# Altium_fpga.net
KiCad netlist of a schematic drawn in Altium Designer
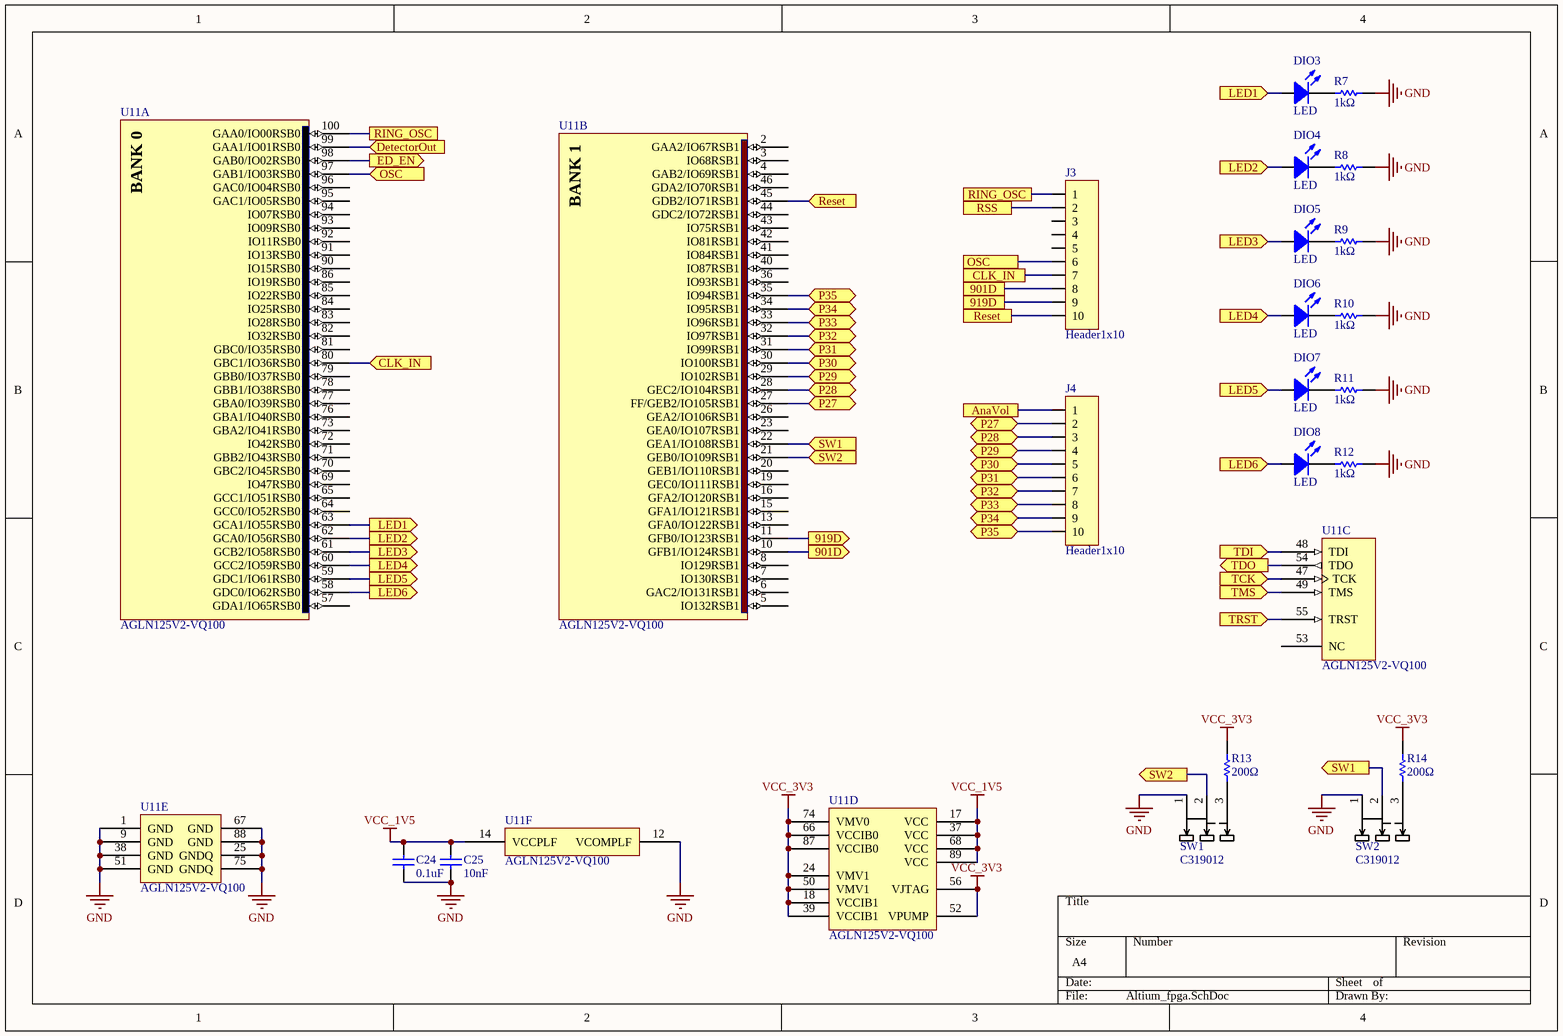
[diagram p0: Altium_fpga.SchDoc]

(export (version "E")
  (design (tool "Eeschema 10.0.6"))
  (components
    (comp (ref "C24") (value "0.1uF") (footprint "C0603") (libsource (lib "backscatter") (part "Cap")))
    (comp (ref "C25") (value "10nF") (footprint "C0603") (libsource (lib "backscatter") (part "Cap")))
    (comp (ref "DIO3") (value "LED") (footprint "LED0603") (libsource (lib "backscatter") (part "LED")))
    (comp (ref "DIO4") (value "LED") (footprint "LED0603") (libsource (lib "backscatter") (part "LED")))
    (comp (ref "DIO5") (value "LED") (footprint "LED0603") (libsource (lib "backscatter") (part "LED")))
    (comp (ref "DIO6") (value "LED") (footprint "LED0603") (libsource (lib "backscatter") (part "LED")))
    (comp (ref "DIO7") (value "LED") (footprint "LED0603") (libsource (lib "backscatter") (part "LED")))
    (comp (ref "DIO8") (value "LED") (footprint "LED0603") (libsource (lib "backscatter") (part "LED")))
    (comp (ref "J3")
      (value "Header1x10")
      (footprint "Header1x10")
      (libsource (lib "backscatter") (part "Header1x10"))
    )
    (comp (ref "J4")
      (value "Header1x10")
      (footprint "Header1x10")
      (libsource (lib "backscatter") (part "Header1x10"))
    )
    (comp (ref "R7") (value "1kΩ") (footprint "R0603") (libsource (lib "backscatter") (part "Res")))
    (comp (ref "R8") (value "1kΩ") (footprint "R0603") (libsource (lib "backscatter") (part "Res")))
    (comp (ref "R9") (value "1kΩ") (footprint "R0603") (libsource (lib "backscatter") (part "Res")))
    (comp (ref "R10") (value "1kΩ") (footprint "R0603") (libsource (lib "backscatter") (part "Res")))
    (comp (ref "R11") (value "1kΩ") (footprint "R0603") (libsource (lib "backscatter") (part "Res")))
    (comp (ref "R12") (value "1kΩ") (footprint "R0603") (libsource (lib "backscatter") (part "Res")))
    (comp (ref "R13") (value "200Ω") (footprint "R0603") (libsource (lib "backscatter") (part "Res")))
    (comp (ref "R14") (value "200Ω") (footprint "R0603") (libsource (lib "backscatter") (part "Res")))
    (comp (ref "SW1")
      (value "C319012")
      (footprint "C319012")
      (libsource (lib "backscatter") (part "C319012"))
    )
    (comp (ref "SW2")
      (value "C319012")
      (footprint "C319012")
      (libsource (lib "backscatter") (part "C319012"))
    )
    (comp (ref "U11")
      (value "AGLN125V2-VQ100")
      (footprint "VQ100_N")
      (libsource (lib "Actel IGLOO nano") (part "AGLN125V2-VQ100"))
    )
  )
  (nets
    (net (code "1") (name "/901D") (class "Default")
      (node (ref "J3") (pin "8") (pinfunction "8_8") (pintype "passive"))
      (node (ref "U11") (pin "10") (pinfunction "GFB1/IO124RSB1_10") (pintype "bidirectional"))
    )
    (net (code "2") (name "/919D") (class "Default")
      (node (ref "J3") (pin "9") (pinfunction "9_9") (pintype "passive"))
      (node (ref "U11") (pin "11") (pinfunction "GFB0/IO123RSB1_11") (pintype "bidirectional"))
    )
    (net (code "3") (name "/AnaVol") (class "Default")
      (node (ref "J4") (pin "1") (pinfunction "1_1") (pintype "passive"))
    )
    (net (code "4") (name "/CLK_IN") (class "Default")
      (node (ref "J3") (pin "7") (pinfunction "7_7") (pintype "passive"))
      (node (ref "U11") (pin "80") (pinfunction "GBC1/IO36RSB0_80") (pintype "bidirectional"))
    )
    (net (code "5") (name "/DetectorOut") (class "Default")
      (node (ref "U11") (pin "99") (pinfunction "GAA1/IO01RSB0_99") (pintype "bidirectional"))
    )
    (net (code "6") (name "/ED_EN") (class "Default")
      (node (ref "U11") (pin "98") (pinfunction "GAB0/IO02RSB0_98") (pintype "bidirectional"))
    )
    (net (code "7") (name "/LED1") (class "Default")
      (node (ref "DIO3") (pin "1") (pinfunction "*_1") (pintype "passive"))
      (node (ref "U11") (pin "63") (pinfunction "GCA1/IO55RSB0_63") (pintype "bidirectional"))
    )
    (net (code "8") (name "/LED2") (class "Default")
      (node (ref "DIO4") (pin "1") (pinfunction "*_1") (pintype "passive"))
      (node (ref "U11") (pin "62") (pinfunction "GCA0/IO56RSB0_62") (pintype "bidirectional"))
    )
    (net (code "9") (name "/LED3") (class "Default")
      (node (ref "DIO5") (pin "1") (pinfunction "*_1") (pintype "passive"))
      (node (ref "U11") (pin "61") (pinfunction "GCB2/IO58RSB0_61") (pintype "bidirectional"))
    )
    (net (code "10") (name "/LED4") (class "Default")
      (node (ref "DIO6") (pin "1") (pinfunction "*_1") (pintype "passive"))
      (node (ref "U11") (pin "60") (pinfunction "GCC2/IO59RSB0_60") (pintype "bidirectional"))
    )
    (net (code "11") (name "/LED5") (class "Default")
      (node (ref "DIO7") (pin "1") (pinfunction "*_1") (pintype "passive"))
      (node (ref "U11") (pin "59") (pinfunction "GDC1/IO61RSB0_59") (pintype "bidirectional"))
    )
    (net (code "12") (name "/LED6") (class "Default")
      (node (ref "DIO8") (pin "1") (pinfunction "*_1") (pintype "passive"))
      (node (ref "U11") (pin "58") (pinfunction "GDC0/IO62RSB0_58") (pintype "bidirectional"))
    )
    (net (code "13") (name "/OSC") (class "Default")
      (node (ref "J3") (pin "6") (pinfunction "6_6") (pintype "passive"))
      (node (ref "U11") (pin "97") (pinfunction "GAB1/IO03RSB0_97") (pintype "bidirectional"))
    )
    (net (code "14") (name "/P27") (class "Default")
      (node (ref "J4") (pin "2") (pinfunction "2_2") (pintype "passive"))
      (node (ref "U11") (pin "27") (pinfunction "FF/GEB2/IO105RSB1_27") (pintype "bidirectional"))
    )
    (net (code "15") (name "/P28") (class "Default")
      (node (ref "J4") (pin "3") (pinfunction "3_3") (pintype "passive"))
      (node (ref "U11") (pin "28") (pinfunction "GEC2/IO104RSB1_28") (pintype "bidirectional"))
    )
    (net (code "16") (name "/P29") (class "Default")
      (node (ref "J4") (pin "4") (pinfunction "4_4") (pintype "passive"))
      (node (ref "U11") (pin "29") (pinfunction "IO102RSB1_29") (pintype "bidirectional"))
    )
    (net (code "17") (name "/P30") (class "Default")
      (node (ref "J4") (pin "5") (pinfunction "5_5") (pintype "passive"))
      (node (ref "U11") (pin "30") (pinfunction "IO100RSB1_30") (pintype "bidirectional"))
    )
    (net (code "18") (name "/P31") (class "Default")
      (node (ref "J4") (pin "6") (pinfunction "6_6") (pintype "passive"))
      (node (ref "U11") (pin "31") (pinfunction "IO99RSB1_31") (pintype "bidirectional"))
    )
    (net (code "19") (name "/P32") (class "Default")
      (node (ref "J4") (pin "7") (pinfunction "7_7") (pintype "passive"))
      (node (ref "U11") (pin "32") (pinfunction "IO97RSB1_32") (pintype "bidirectional"))
    )
    (net (code "20") (name "/P33") (class "Default")
      (node (ref "J4") (pin "8") (pinfunction "8_8") (pintype "passive"))
      (node (ref "U11") (pin "33") (pinfunction "IO96RSB1_33") (pintype "bidirectional"))
    )
    (net (code "21") (name "/P34") (class "Default")
      (node (ref "J4") (pin "9") (pinfunction "9_9") (pintype "passive"))
      (node (ref "U11") (pin "34") (pinfunction "IO95RSB1_34") (pintype "bidirectional"))
    )
    (net (code "22") (name "/P35") (class "Default")
      (node (ref "J4") (pin "10") (pinfunction "10_10") (pintype "passive"))
      (node (ref "U11") (pin "35") (pinfunction "IO94RSB1_35") (pintype "bidirectional"))
    )
    (net (code "23") (name "/RING_OSC") (class "Default")
      (node (ref "J3") (pin "1") (pinfunction "1_1") (pintype "passive"))
      (node (ref "U11") (pin "100") (pinfunction "GAA0/IO00RSB0_100") (pintype "bidirectional"))
    )
    (net (code "24") (name "/RSS") (class "Default")
      (node (ref "J3") (pin "2") (pinfunction "2_2") (pintype "passive"))
    )
    (net (code "25") (name "/Reset") (class "Default")
      (node (ref "J3") (pin "10") (pinfunction "10_10") (pintype "passive"))
      (node (ref "U11") (pin "45") (pinfunction "GDB2/IO71RSB1_45") (pintype "bidirectional"))
    )
    (net (code "26") (name "/SW1") (class "Default")
      (node (ref "SW2") (pin "2") (pinfunction "2_2") (pintype "passive"))
      (node (ref "U11") (pin "22") (pinfunction "GEA1/IO108RSB1_22") (pintype "bidirectional"))
    )
    (net (code "27") (name "/SW2") (class "Default")
      (node (ref "SW1") (pin "2") (pinfunction "2_2") (pintype "passive"))
      (node (ref "U11") (pin "21") (pinfunction "GEB0/IO109RSB1_21") (pintype "bidirectional"))
    )
    (net (code "28") (name "/TCK") (class "Default")
      (node (ref "U11") (pin "47") (pinfunction "TCK_47") (pintype "input"))
    )
    (net (code "29") (name "/TDI") (class "Default")
      (node (ref "U11") (pin "48") (pinfunction "TDI_48") (pintype "input"))
    )
    (net (code "30") (name "/TDO") (class "Default")
      (node (ref "U11") (pin "54") (pinfunction "TDO_54") (pintype "output"))
    )
    (net (code "31") (name "/TMS") (class "Default")
      (node (ref "U11") (pin "49") (pinfunction "TMS_49") (pintype "input"))
    )
    (net (code "32") (name "/TRST") (class "Default")
      (node (ref "U11") (pin "55") (pinfunction "TRST_55") (pintype "input"))
    )
    (net (code "33") (name "GND") (class "Default")
      (node (ref "C24") (pin "2") (pinfunction "2_2") (pintype "passive"))
      (node (ref "C25") (pin "2") (pinfunction "2_2") (pintype "passive"))
      (node (ref "R10") (pin "1") (pinfunction "1_1") (pintype "passive"))
      (node (ref "R11") (pin "1") (pinfunction "1_1") (pintype "passive"))
      (node (ref "R12") (pin "1") (pinfunction "1_1") (pintype "passive"))
      (node (ref "R7") (pin "1") (pinfunction "1_1") (pintype "passive"))
      (node (ref "R8") (pin "1") (pinfunction "1_1") (pintype "passive"))
      (node (ref "R9") (pin "1") (pinfunction "1_1") (pintype "passive"))
      (node (ref "SW1") (pin "1") (pinfunction "1_1") (pintype "passive"))
      (node (ref "SW2") (pin "1") (pinfunction "1_1") (pintype "passive"))
      (node (ref "U11") (pin "1") (pinfunction "GND_1") (pintype "power_in"))
      (node (ref "U11") (pin "12") (pinfunction "VCOMPLF_12") (pintype "power_in"))
      (node (ref "U11") (pin "25") (pinfunction "GNDQ_25") (pintype "power_in"))
      (node (ref "U11") (pin "38") (pinfunction "GND_38") (pintype "power_in"))
      (node (ref "U11") (pin "51") (pinfunction "GND_51") (pintype "power_in"))
      (node (ref "U11") (pin "67") (pinfunction "GND_67") (pintype "power_in"))
      (node (ref "U11") (pin "75") (pinfunction "GNDQ_75") (pintype "power_in"))
      (node (ref "U11") (pin "88") (pinfunction "GND_88") (pintype "power_in"))
      (node (ref "U11") (pin "9") (pinfunction "GND_9") (pintype "power_in"))
    )
    (net (code "34") (name "Net-(DIO3-*-Pad2)") (class "Default")
      (node (ref "DIO3") (pin "2") (pinfunction "*_2") (pintype "passive"))
      (node (ref "R7") (pin "2") (pinfunction "2_2") (pintype "passive"))
    )
    (net (code "35") (name "Net-(DIO4-*-Pad2)") (class "Default")
      (node (ref "DIO4") (pin "2") (pinfunction "*_2") (pintype "passive"))
      (node (ref "R8") (pin "2") (pinfunction "2_2") (pintype "passive"))
    )
    (net (code "36") (name "Net-(DIO5-*-Pad2)") (class "Default")
      (node (ref "DIO5") (pin "2") (pinfunction "*_2") (pintype "passive"))
      (node (ref "R9") (pin "2") (pinfunction "2_2") (pintype "passive"))
    )
    (net (code "37") (name "Net-(DIO6-*-Pad2)") (class "Default")
      (node (ref "DIO6") (pin "2") (pinfunction "*_2") (pintype "passive"))
      (node (ref "R10") (pin "2") (pinfunction "2_2") (pintype "passive"))
    )
    (net (code "38") (name "Net-(DIO7-*-Pad2)") (class "Default")
      (node (ref "DIO7") (pin "2") (pinfunction "*_2") (pintype "passive"))
      (node (ref "R11") (pin "2") (pinfunction "2_2") (pintype "passive"))
    )
    (net (code "39") (name "Net-(DIO8-*-Pad2)") (class "Default")
      (node (ref "DIO8") (pin "2") (pinfunction "*_2") (pintype "passive"))
      (node (ref "R12") (pin "2") (pinfunction "2_2") (pintype "passive"))
    )
    (net (code "40") (name "Net-(R13-Pad2)") (class "Default")
      (node (ref "R13") (pin "2") (pinfunction "2_2") (pintype "passive"))
      (node (ref "SW1") (pin "3") (pinfunction "3_3") (pintype "passive"))
    )
    (net (code "41") (name "Net-(R14-Pad2)") (class "Default")
      (node (ref "R14") (pin "2") (pinfunction "2_2") (pintype "passive"))
      (node (ref "SW2") (pin "3") (pinfunction "3_3") (pintype "passive"))
    )
    (net (code "42") (name "VCC_1V5") (class "Default")
      (node (ref "C24") (pin "1") (pinfunction "1_1") (pintype "passive"))
      (node (ref "C25") (pin "1") (pinfunction "1_1") (pintype "passive"))
      (node (ref "U11") (pin "14") (pinfunction "VCCPLF_14") (pintype "power_in"))
      (node (ref "U11") (pin "17") (pinfunction "VCC_17") (pintype "power_in"))
      (node (ref "U11") (pin "37") (pinfunction "VCC_37") (pintype "power_in"))
      (node (ref "U11") (pin "68") (pinfunction "VCC_68") (pintype "power_in"))
      (node (ref "U11") (pin "89") (pinfunction "VCC_89") (pintype "power_in"))
    )
    (net (code "43") (name "VCC_3V3") (class "Default")
      (node (ref "R13") (pin "1") (pinfunction "1_1") (pintype "passive"))
      (node (ref "R14") (pin "1") (pinfunction "1_1") (pintype "passive"))
      (node (ref "U11") (pin "18") (pinfunction "VCCIB1_18") (pintype "power_in"))
      (node (ref "U11") (pin "24") (pinfunction "VMV1_24") (pintype "power_in"))
      (node (ref "U11") (pin "39") (pinfunction "VCCIB1_39") (pintype "power_in"))
      (node (ref "U11") (pin "50") (pinfunction "VMV1_50") (pintype "power_in"))
      (node (ref "U11") (pin "52") (pinfunction "VPUMP_52") (pintype "power_in"))
      (node (ref "U11") (pin "56") (pinfunction "VJTAG_56") (pintype "power_in"))
      (node (ref "U11") (pin "66") (pinfunction "VCCIB0_66") (pintype "power_in"))
      (node (ref "U11") (pin "74") (pinfunction "VMV0_74") (pintype "power_in"))
      (node (ref "U11") (pin "87") (pinfunction "VCCIB0_87") (pintype "power_in"))
    )
    (net (code "44") (name "unconnected-(J3-Pad3)") (class "Default")
      (node (ref "J3") (pin "3") (pinfunction "3_3") (pintype "passive"))
    )
    (net (code "45") (name "unconnected-(J3-Pad4)") (class "Default")
      (node (ref "J3") (pin "4") (pinfunction "4_4") (pintype "passive"))
    )
    (net (code "46") (name "unconnected-(J3-Pad5)") (class "Default")
      (node (ref "J3") (pin "5") (pinfunction "5_5") (pintype "passive"))
    )
    (net (code "47") (name "unconnected-(U11A-GAC0{slash}IO04RSB0-Pad96)") (class "Default")
      (node (ref "U11") (pin "96") (pinfunction "GAC0/IO04RSB0_96") (pintype "bidirectional"))
    )
    (net (code "48") (name "unconnected-(U11A-GAC1{slash}IO05RSB0-Pad95)") (class "Default")
      (node (ref "U11") (pin "95") (pinfunction "GAC1/IO05RSB0_95") (pintype "bidirectional"))
    )
    (net (code "49") (name "unconnected-(U11A-GBA0{slash}IO39RSB0-Pad77)") (class "Default")
      (node (ref "U11") (pin "77") (pinfunction "GBA0/IO39RSB0_77") (pintype "bidirectional"))
    )
    (net (code "50") (name "unconnected-(U11A-GBA1{slash}IO40RSB0-Pad76)") (class "Default")
      (node (ref "U11") (pin "76") (pinfunction "GBA1/IO40RSB0_76") (pintype "bidirectional"))
    )
    (net (code "51") (name "unconnected-(U11A-GBA2{slash}IO41RSB0-Pad73)") (class "Default")
      (node (ref "U11") (pin "73") (pinfunction "GBA2/IO41RSB0_73") (pintype "bidirectional"))
    )
    (net (code "52") (name "unconnected-(U11A-GBB0{slash}IO37RSB0-Pad79)") (class "Default")
      (node (ref "U11") (pin "79") (pinfunction "GBB0/IO37RSB0_79") (pintype "bidirectional"))
    )
    (net (code "53") (name "unconnected-(U11A-GBB1{slash}IO38RSB0-Pad78)") (class "Default")
      (node (ref "U11") (pin "78") (pinfunction "GBB1/IO38RSB0_78") (pintype "bidirectional"))
    )
    (net (code "54") (name "unconnected-(U11A-GBB2{slash}IO43RSB0-Pad71)") (class "Default")
      (node (ref "U11") (pin "71") (pinfunction "GBB2/IO43RSB0_71") (pintype "bidirectional"))
    )
    (net (code "55") (name "unconnected-(U11A-GBC0{slash}IO35RSB0-Pad81)") (class "Default")
      (node (ref "U11") (pin "81") (pinfunction "GBC0/IO35RSB0_81") (pintype "bidirectional"))
    )
    (net (code "56") (name "unconnected-(U11A-GBC2{slash}IO45RSB0-Pad70)") (class "Default")
      (node (ref "U11") (pin "70") (pinfunction "GBC2/IO45RSB0_70") (pintype "bidirectional"))
    )
    (net (code "57") (name "unconnected-(U11A-GCC0{slash}IO52RSB0-Pad64)") (class "Default")
      (node (ref "U11") (pin "64") (pinfunction "GCC0/IO52RSB0_64") (pintype "bidirectional"))
    )
    (net (code "58") (name "unconnected-(U11A-GCC1{slash}IO51RSB0-Pad65)") (class "Default")
      (node (ref "U11") (pin "65") (pinfunction "GCC1/IO51RSB0_65") (pintype "bidirectional"))
    )
    (net (code "59") (name "unconnected-(U11A-GDA1{slash}IO65RSB0-Pad57)") (class "Default")
      (node (ref "U11") (pin "57") (pinfunction "GDA1/IO65RSB0_57") (pintype "bidirectional"))
    )
    (net (code "60") (name "unconnected-(U11A-IO07RSB0-Pad94)") (class "Default")
      (node (ref "U11") (pin "94") (pinfunction "IO07RSB0_94") (pintype "bidirectional"))
    )
    (net (code "61") (name "unconnected-(U11A-IO09RSB0-Pad93)") (class "Default")
      (node (ref "U11") (pin "93") (pinfunction "IO09RSB0_93") (pintype "bidirectional"))
    )
    (net (code "62") (name "unconnected-(U11A-IO11RSB0-Pad92)") (class "Default")
      (node (ref "U11") (pin "92") (pinfunction "IO11RSB0_92") (pintype "bidirectional"))
    )
    (net (code "63") (name "unconnected-(U11A-IO13RSB0-Pad91)") (class "Default")
      (node (ref "U11") (pin "91") (pinfunction "IO13RSB0_91") (pintype "bidirectional"))
    )
    (net (code "64") (name "unconnected-(U11A-IO15RSB0-Pad90)") (class "Default")
      (node (ref "U11") (pin "90") (pinfunction "IO15RSB0_90") (pintype "bidirectional"))
    )
    (net (code "65") (name "unconnected-(U11A-IO19RSB0-Pad86)") (class "Default")
      (node (ref "U11") (pin "86") (pinfunction "IO19RSB0_86") (pintype "bidirectional"))
    )
    (net (code "66") (name "unconnected-(U11A-IO22RSB0-Pad85)") (class "Default")
      (node (ref "U11") (pin "85") (pinfunction "IO22RSB0_85") (pintype "bidirectional"))
    )
    (net (code "67") (name "unconnected-(U11A-IO25RSB0-Pad84)") (class "Default")
      (node (ref "U11") (pin "84") (pinfunction "IO25RSB0_84") (pintype "bidirectional"))
    )
    (net (code "68") (name "unconnected-(U11A-IO28RSB0-Pad83)") (class "Default")
      (node (ref "U11") (pin "83") (pinfunction "IO28RSB0_83") (pintype "bidirectional"))
    )
    (net (code "69") (name "unconnected-(U11A-IO32RSB0-Pad82)") (class "Default")
      (node (ref "U11") (pin "82") (pinfunction "IO32RSB0_82") (pintype "bidirectional"))
    )
    (net (code "70") (name "unconnected-(U11A-IO42RSB0-Pad72)") (class "Default")
      (node (ref "U11") (pin "72") (pinfunction "IO42RSB0_72") (pintype "bidirectional"))
    )
    (net (code "71") (name "unconnected-(U11A-IO47RSB0-Pad69)") (class "Default")
      (node (ref "U11") (pin "69") (pinfunction "IO47RSB0_69") (pintype "bidirectional"))
    )
    (net (code "72") (name "unconnected-(U11B-GAA2{slash}IO67RSB1-Pad2)") (class "Default")
      (node (ref "U11") (pin "2") (pinfunction "GAA2/IO67RSB1_2") (pintype "bidirectional"))
    )
    (net (code "73") (name "unconnected-(U11B-GAB2{slash}IO69RSB1-Pad4)") (class "Default")
      (node (ref "U11") (pin "4") (pinfunction "GAB2/IO69RSB1_4") (pintype "bidirectional"))
    )
    (net (code "74") (name "unconnected-(U11B-GAC2{slash}IO131RSB1-Pad6)") (class "Default")
      (node (ref "U11") (pin "6") (pinfunction "GAC2/IO131RSB1_6") (pintype "bidirectional"))
    )
    (net (code "75") (name "unconnected-(U11B-GDA2{slash}IO70RSB1-Pad46)") (class "Default")
      (node (ref "U11") (pin "46") (pinfunction "GDA2/IO70RSB1_46") (pintype "bidirectional"))
    )
    (net (code "76") (name "unconnected-(U11B-GDC2{slash}IO72RSB1-Pad44)") (class "Default")
      (node (ref "U11") (pin "44") (pinfunction "GDC2/IO72RSB1_44") (pintype "bidirectional"))
    )
    (net (code "77") (name "unconnected-(U11B-GEA0{slash}IO107RSB1-Pad23)") (class "Default")
      (node (ref "U11") (pin "23") (pinfunction "GEA0/IO107RSB1_23") (pintype "bidirectional"))
    )
    (net (code "78") (name "unconnected-(U11B-GEA2{slash}IO106RSB1-Pad26)") (class "Default")
      (node (ref "U11") (pin "26") (pinfunction "GEA2/IO106RSB1_26") (pintype "bidirectional"))
    )
    (net (code "79") (name "unconnected-(U11B-GEB1{slash}IO110RSB1-Pad20)") (class "Default")
      (node (ref "U11") (pin "20") (pinfunction "GEB1/IO110RSB1_20") (pintype "bidirectional"))
    )
    (net (code "80") (name "unconnected-(U11B-GEC0{slash}IO111RSB1-Pad19)") (class "Default")
      (node (ref "U11") (pin "19") (pinfunction "GEC0/IO111RSB1_19") (pintype "bidirectional"))
    )
    (net (code "81") (name "unconnected-(U11B-GFA0{slash}IO122RSB1-Pad13)") (class "Default")
      (node (ref "U11") (pin "13") (pinfunction "GFA0/IO122RSB1_13") (pintype "bidirectional"))
    )
    (net (code "82") (name "unconnected-(U11B-GFA1{slash}IO121RSB1-Pad15)") (class "Default")
      (node (ref "U11") (pin "15") (pinfunction "GFA1/IO121RSB1_15") (pintype "bidirectional"))
    )
    (net (code "83") (name "unconnected-(U11B-GFA2{slash}IO120RSB1-Pad16)") (class "Default")
      (node (ref "U11") (pin "16") (pinfunction "GFA2/IO120RSB1_16") (pintype "bidirectional"))
    )
    (net (code "84") (name "unconnected-(U11B-IO68RSB1-Pad3)") (class "Default")
      (node (ref "U11") (pin "3") (pinfunction "IO68RSB1_3") (pintype "bidirectional"))
    )
    (net (code "85") (name "unconnected-(U11B-IO75RSB1-Pad43)") (class "Default")
      (node (ref "U11") (pin "43") (pinfunction "IO75RSB1_43") (pintype "bidirectional"))
    )
    (net (code "86") (name "unconnected-(U11B-IO81RSB1-Pad42)") (class "Default")
      (node (ref "U11") (pin "42") (pinfunction "IO81RSB1_42") (pintype "bidirectional"))
    )
    (net (code "87") (name "unconnected-(U11B-IO84RSB1-Pad41)") (class "Default")
      (node (ref "U11") (pin "41") (pinfunction "IO84RSB1_41") (pintype "bidirectional"))
    )
    (net (code "88") (name "unconnected-(U11B-IO87RSB1-Pad40)") (class "Default")
      (node (ref "U11") (pin "40") (pinfunction "IO87RSB1_40") (pintype "bidirectional"))
    )
    (net (code "89") (name "unconnected-(U11B-IO93RSB1-Pad36)") (class "Default")
      (node (ref "U11") (pin "36") (pinfunction "IO93RSB1_36") (pintype "bidirectional"))
    )
    (net (code "90") (name "unconnected-(U11B-IO129RSB1-Pad8)") (class "Default")
      (node (ref "U11") (pin "8") (pinfunction "IO129RSB1_8") (pintype "bidirectional"))
    )
    (net (code "91") (name "unconnected-(U11B-IO130RSB1-Pad7)") (class "Default")
      (node (ref "U11") (pin "7") (pinfunction "IO130RSB1_7") (pintype "bidirectional"))
    )
    (net (code "92") (name "unconnected-(U11B-IO132RSB1-Pad5)") (class "Default")
      (node (ref "U11") (pin "5") (pinfunction "IO132RSB1_5") (pintype "bidirectional"))
    )
    (net (code "93") (name "unconnected-(U11C-NC-Pad53)") (class "Default")
      (node (ref "U11") (pin "53") (pinfunction "NC_53") (pintype "passive"))
    )
  )
)
